# v0_1.net
KiCad netlist of a schematic drawn in EAGLE
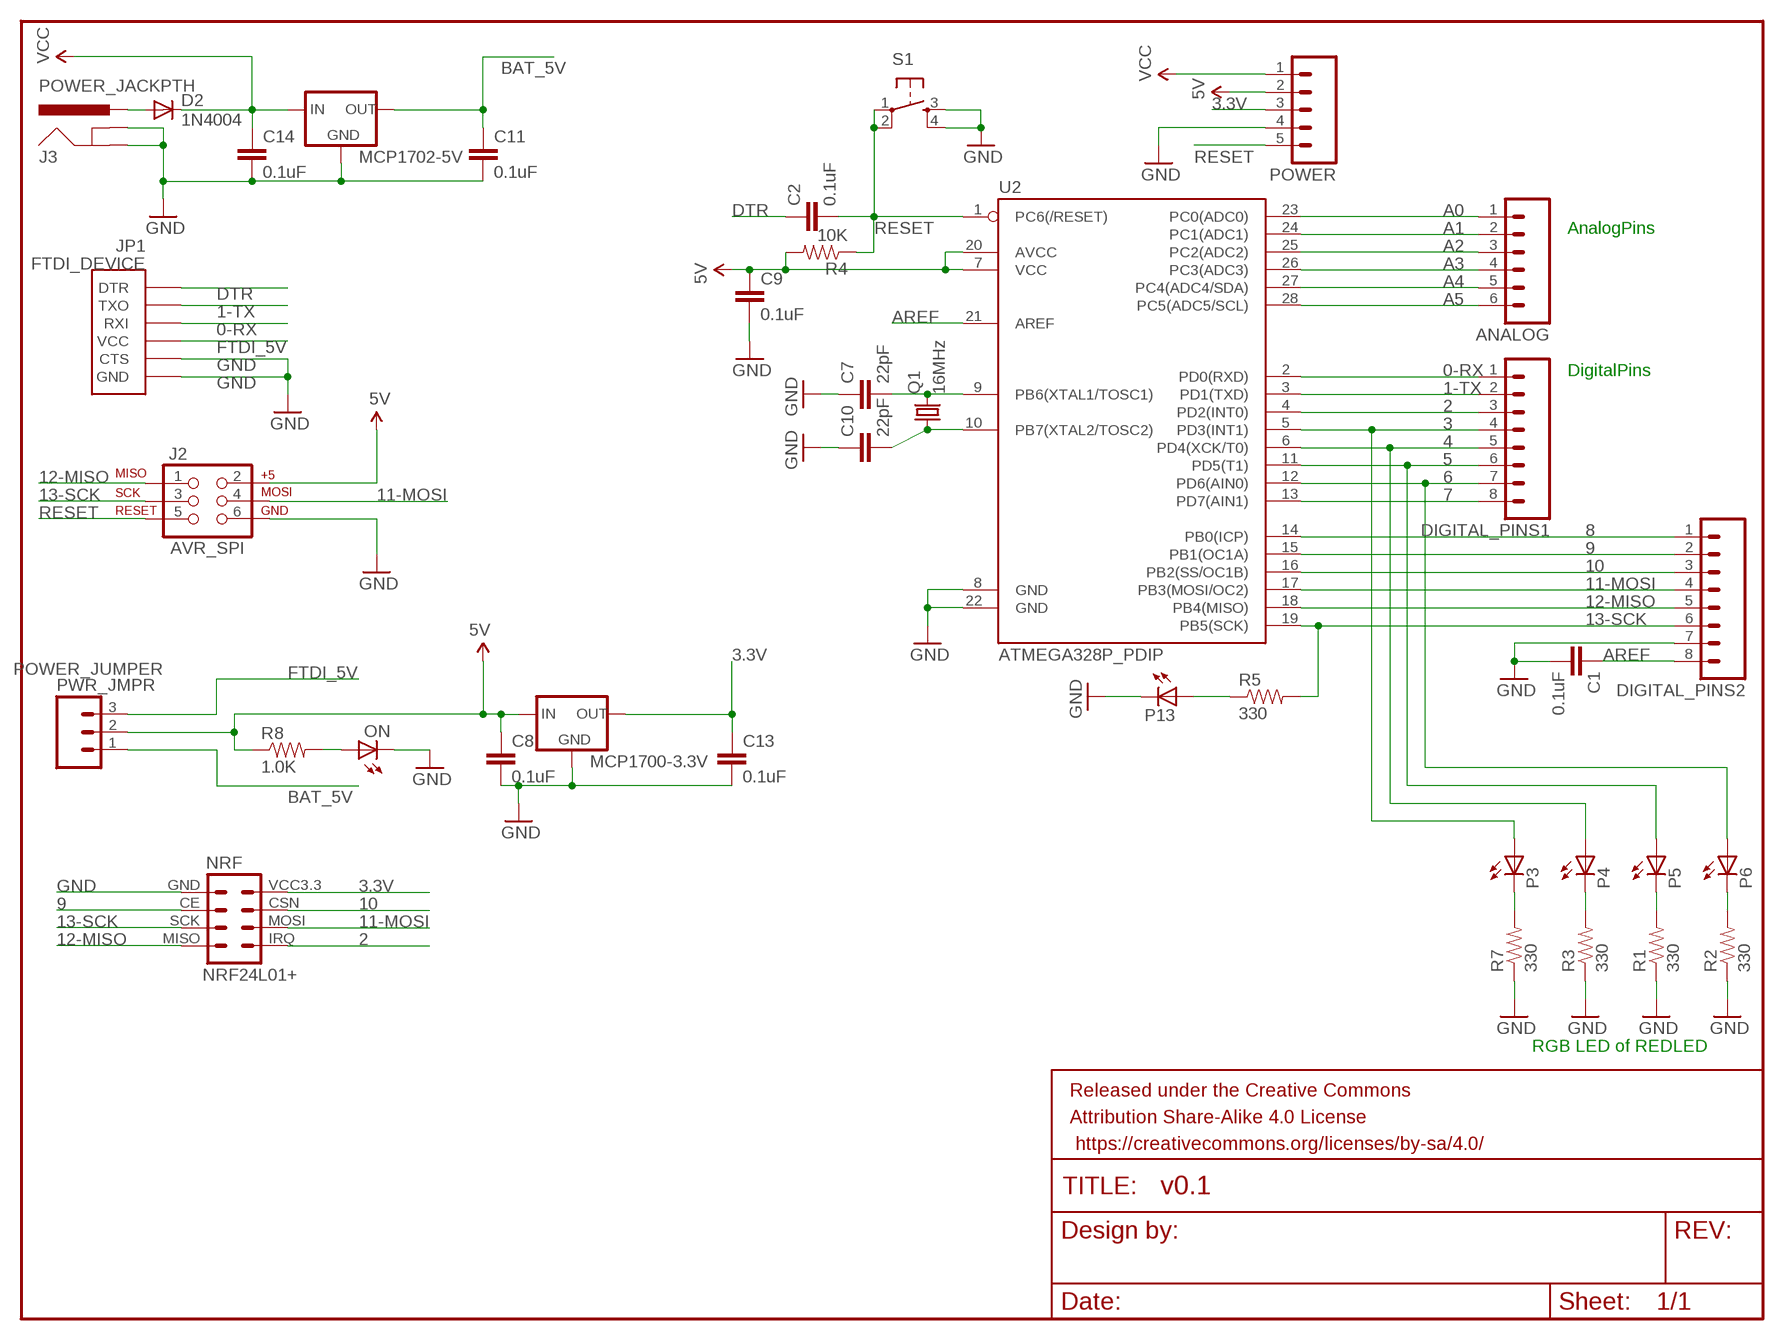
[diagram p0: schematic, sheet 1]

(export (version "E")
  (design (tool "Eeschema 10.0.6"))
  (components
    (comp (ref "ANALOG")
      (value "M06LOCK")
      (footprint "eagle-import:1X06_LOCK")
      (libsource (lib "eagle-import") (part "M06LOCK"))
    )
    (comp (ref "C1")
      (value "0.1uF")
      (footprint "eagle-import:CAP-PTH-SMALL")
      (libsource (lib "eagle-import") (part "CAPPTH"))
    )
    (comp (ref "C2")
      (value "0.1uF")
      (footprint "eagle-import:CAP-PTH-SMALL")
      (libsource (lib "eagle-import") (part "CAPPTH"))
    )
    (comp (ref "C7")
      (value "22pF")
      (footprint "eagle-import:CAP-PTH-SMALL")
      (libsource (lib "eagle-import") (part "CAPPTH"))
    )
    (comp (ref "C8")
      (value "0.1uF")
      (footprint "eagle-import:CAP-PTH-SMALL")
      (libsource (lib "eagle-import") (part "CAPPTH"))
    )
    (comp (ref "C9")
      (value "0.1uF")
      (footprint "eagle-import:CAP-PTH-SMALL")
      (libsource (lib "eagle-import") (part "CAPPTH"))
    )
    (comp (ref "C10")
      (value "22pF")
      (footprint "eagle-import:CAP-PTH-SMALL")
      (libsource (lib "eagle-import") (part "CAPPTH"))
    )
    (comp (ref "C11")
      (value "0.1uF")
      (footprint "eagle-import:CAP-PTH-SMALL")
      (libsource (lib "eagle-import") (part "CAPPTH"))
    )
    (comp (ref "C13")
      (value "0.1uF")
      (footprint "eagle-import:CAP-PTH-SMALL")
      (libsource (lib "eagle-import") (part "CAPPTH"))
    )
    (comp (ref "C14")
      (value "0.1uF")
      (footprint "eagle-import:CAP-PTH-SMALL")
      (libsource (lib "eagle-import") (part "CAPPTH"))
    )
    (comp (ref "D2")
      (value "1N4004")
      (footprint "eagle-import:DO41-10")
      (libsource (lib "eagle-import") (part "1N4004"))
    )
    (comp (ref "DIGITAL_PINS1")
      (value "M08LOCK")
      (footprint "eagle-import:1X08_LOCK")
      (libsource (lib "eagle-import") (part "M08LOCK"))
    )
    (comp (ref "DIGITAL_PINS2")
      (value "M08LOCK")
      (footprint "eagle-import:1X08_LOCK")
      (libsource (lib "eagle-import") (part "M08LOCK"))
    )
    (comp (ref "FRAME1")
      (value "FRAME-LETTER")
      (footprint "eagle-import:CREATIVE_COMMONS")
      (libsource (lib "eagle-import") (part "FRAME-LETTER"))
    )
    (comp (ref "J2")
      (value "AVR_SPI")
      (footprint "eagle-import:2X3")
      (libsource (lib "eagle-import") (part "AVR_SPI_PRG_6PTH"))
    )
    (comp (ref "J3")
      (value "POWER_JACKPTH")
      (footprint "eagle-import:POWER_JACK_PTH")
      (libsource (lib "eagle-import") (part "POWER_JACKPTH"))
    )
    (comp (ref "JP1")
      (value "FTDI_DEVICE")
      (footprint "eagle-import:FTDI_DEVICE_SIDE")
      (libsource (lib "eagle-import") (part "FTDI_DEVICE"))
    )
    (comp (ref "MCP1700-3.3V")
      (value "MCP1700INLINE")
      (footprint "eagle-import:TO92-INLINE")
      (libsource (lib "eagle-import") (part "MCP1700INLINE"))
    )
    (comp (ref "MCP1702-5V")
      (value "MCP1700INLINE")
      (footprint "eagle-import:TO92-INLINE")
      (libsource (lib "eagle-import") (part "MCP1700INLINE"))
    )
    (comp (ref "NRF")
      (value "NRF24L01+")
      (footprint "eagle-import:2X4")
      (libsource (lib "eagle-import") (part "NRF24L01+"))
    )
    (comp (ref "ON")
      (value "LED3MM")
      (footprint "eagle-import:LED3MM")
      (libsource (lib "eagle-import") (part "LED3MM"))
    )
    (comp (ref "P3")
      (value "LED5MM")
      (footprint "eagle-import:LED5MM")
      (libsource (lib "eagle-import") (part "LED5MM"))
    )
    (comp (ref "P4")
      (value "LED5MM")
      (footprint "eagle-import:LED5MM")
      (libsource (lib "eagle-import") (part "LED5MM"))
    )
    (comp (ref "P5")
      (value "LED5MM")
      (footprint "eagle-import:LED5MM")
      (libsource (lib "eagle-import") (part "LED5MM"))
    )
    (comp (ref "P6")
      (value "LED5MM")
      (footprint "eagle-import:LED5MM")
      (libsource (lib "eagle-import") (part "LED5MM"))
    )
    (comp (ref "P13")
      (value "LED3MM")
      (footprint "eagle-import:LED3MM")
      (libsource (lib "eagle-import") (part "LED3MM"))
    )
    (comp (ref "POWER")
      (value "M05LOCK")
      (footprint "eagle-import:1X05_LOCK")
      (libsource (lib "eagle-import") (part "M05LOCK"))
    )
    (comp (ref "PWR_JMPR")
      (value "M03LOCK")
      (footprint "eagle-import:1X03_LOCK")
      (libsource (lib "eagle-import") (part "M03LOCK"))
    )
    (comp (ref "Q1")
      (value "16MHz")
      (footprint "eagle-import:HC49_S")
      (libsource (lib "eagle-import") (part "CRYSTALHC49S"))
    )
    (comp (ref "R1")
      (value "330")
      (footprint "eagle-import:AXIAL-0.4")
      (libsource (lib "eagle-import") (part "RESISTORPTH-1/4W"))
    )
    (comp (ref "R2")
      (value "330")
      (footprint "eagle-import:AXIAL-0.4")
      (libsource (lib "eagle-import") (part "RESISTORPTH-1/4W"))
    )
    (comp (ref "R3")
      (value "330")
      (footprint "eagle-import:AXIAL-0.4")
      (libsource (lib "eagle-import") (part "RESISTORPTH-1/4W"))
    )
    (comp (ref "R4")
      (value "10K")
      (footprint "eagle-import:AXIAL-0.4")
      (libsource (lib "eagle-import") (part "RESISTORPTH-1/4W"))
    )
    (comp (ref "R5")
      (value "330")
      (footprint "eagle-import:AXIAL-0.4")
      (libsource (lib "eagle-import") (part "RESISTORPTH-1/4W"))
    )
    (comp (ref "R7")
      (value "330")
      (footprint "eagle-import:AXIAL-0.4")
      (libsource (lib "eagle-import") (part "RESISTORPTH-1/4W"))
    )
    (comp (ref "R8")
      (value "1.0K")
      (footprint "eagle-import:AXIAL-0.4")
      (libsource (lib "eagle-import") (part "RESISTORPTH-1/4W"))
    )
    (comp (ref "S1")
      (value "TAC_SWITCHPTH")
      (footprint "eagle-import:TACTILE-PTH")
      (libsource (lib "eagle-import") (part "TAC_SWITCHPTH"))
    )
    (comp (ref "U2")
      (value "ATMEGA328P_PDIP")
      (footprint "eagle-import:DIL28-3")
      (libsource (lib "eagle-import") (part "ATMEGA328P_PDIP"))
    )
  )
  (nets
    (net (code "1") (name "/0-RX") (class "Default")
      (node (ref "DIGITAL_PINS1") (pin "1") (pinfunction "1_1") (pintype "passive"))
      (node (ref "JP1") (pin "P$3") (pinfunction "RXI_P$3") (pintype "bidirectional"))
      (node (ref "U2") (pin "2") (pinfunction "PD0(RXD)_2") (pintype "bidirectional"))
    )
    (net (code "2") (name "/1-TX") (class "Default")
      (node (ref "DIGITAL_PINS1") (pin "2") (pinfunction "2_2") (pintype "passive"))
      (node (ref "JP1") (pin "P$2") (pinfunction "TXO_P$2") (pintype "bidirectional"))
      (node (ref "U2") (pin "3") (pinfunction "PD1(TXD)_3") (pintype "bidirectional"))
    )
    (net (code "3") (name "/2") (class "Default")
      (node (ref "DIGITAL_PINS1") (pin "3") (pinfunction "3_3") (pintype "passive"))
      (node (ref "NRF") (pin "IRQ") (pinfunction "IRQ_IRQ") (pintype "passive"))
      (node (ref "U2") (pin "4") (pinfunction "PD2(INT0)_4") (pintype "bidirectional"))
    )
    (net (code "4") (name "/3") (class "Default")
      (node (ref "DIGITAL_PINS1") (pin "4") (pinfunction "4_4") (pintype "passive"))
      (node (ref "P3") (pin "A") (pinfunction "A_A") (pintype "passive"))
      (node (ref "U2") (pin "5") (pinfunction "PD3(INT1)_5") (pintype "bidirectional"))
    )
    (net (code "5") (name "/3.3V") (class "Default")
      (node (ref "C13") (pin "1") (pinfunction "1_1") (pintype "passive"))
      (node (ref "MCP1700-3.3V") (pin "3") (pinfunction "OUT_3") (pintype "passive"))
      (node (ref "NRF") (pin "VCC3.3") (pinfunction "VCC_VCC3.3") (pintype "passive"))
      (node (ref "POWER") (pin "3") (pinfunction "3_3") (pintype "passive"))
    )
    (net (code "6") (name "/4") (class "Default")
      (node (ref "DIGITAL_PINS1") (pin "5") (pinfunction "5_5") (pintype "passive"))
      (node (ref "P4") (pin "A") (pinfunction "A_A") (pintype "passive"))
      (node (ref "U2") (pin "6") (pinfunction "PD4(XCK/T0)_6") (pintype "bidirectional"))
    )
    (net (code "7") (name "/5") (class "Default")
      (node (ref "DIGITAL_PINS1") (pin "6") (pinfunction "6_6") (pintype "passive"))
      (node (ref "P5") (pin "A") (pinfunction "A_A") (pintype "passive"))
      (node (ref "U2") (pin "11") (pinfunction "PD5(T1)_11") (pintype "bidirectional"))
    )
    (net (code "8") (name "/6") (class "Default")
      (node (ref "DIGITAL_PINS1") (pin "7") (pinfunction "7_7") (pintype "passive"))
      (node (ref "P6") (pin "A") (pinfunction "A_A") (pintype "passive"))
      (node (ref "U2") (pin "12") (pinfunction "PD6(AIN0)_12") (pintype "bidirectional"))
    )
    (net (code "9") (name "/7") (class "Default")
      (node (ref "DIGITAL_PINS1") (pin "8") (pinfunction "8_8") (pintype "passive"))
      (node (ref "U2") (pin "13") (pinfunction "PD7(AIN1)_13") (pintype "bidirectional"))
    )
    (net (code "10") (name "/8") (class "Default")
      (node (ref "DIGITAL_PINS2") (pin "1") (pinfunction "1_1") (pintype "passive"))
      (node (ref "U2") (pin "14") (pinfunction "PB0(ICP)_14") (pintype "bidirectional"))
    )
    (net (code "11") (name "/9") (class "Default")
      (node (ref "DIGITAL_PINS2") (pin "2") (pinfunction "2_2") (pintype "passive"))
      (node (ref "NRF") (pin "CE") (pinfunction "CE_CE") (pintype "passive"))
      (node (ref "U2") (pin "15") (pinfunction "PB1(OC1A)_15") (pintype "bidirectional"))
    )
    (net (code "12") (name "/10") (class "Default")
      (node (ref "DIGITAL_PINS2") (pin "3") (pinfunction "3_3") (pintype "passive"))
      (node (ref "NRF") (pin "CSN") (pinfunction "CSN_CSN") (pintype "passive"))
      (node (ref "U2") (pin "16") (pinfunction "PB2(SS/OC1B)_16") (pintype "bidirectional"))
    )
    (net (code "13") (name "/11-MOSI") (class "Default")
      (node (ref "DIGITAL_PINS2") (pin "4") (pinfunction "4_4") (pintype "passive"))
      (node (ref "J2") (pin "4") (pinfunction "4_4") (pintype "passive"))
      (node (ref "NRF") (pin "MOSI") (pinfunction "MOSI_MOSI") (pintype "passive"))
      (node (ref "U2") (pin "17") (pinfunction "PB3(MOSI/OC2)_17") (pintype "bidirectional"))
    )
    (net (code "14") (name "/12-MISO") (class "Default")
      (node (ref "DIGITAL_PINS2") (pin "5") (pinfunction "5_5") (pintype "passive"))
      (node (ref "J2") (pin "1") (pinfunction "1_1") (pintype "passive"))
      (node (ref "NRF") (pin "MISO") (pinfunction "MISO_MISO") (pintype "passive"))
      (node (ref "U2") (pin "18") (pinfunction "PB4(MISO)_18") (pintype "bidirectional"))
    )
    (net (code "15") (name "/13-SCK") (class "Default")
      (node (ref "DIGITAL_PINS2") (pin "6") (pinfunction "6_6") (pintype "passive"))
      (node (ref "J2") (pin "3") (pinfunction "3_3") (pintype "passive"))
      (node (ref "NRF") (pin "SCK") (pinfunction "SCK_SCK") (pintype "passive"))
      (node (ref "R5") (pin "P$2") (pinfunction "2_P$2") (pintype "passive"))
      (node (ref "U2") (pin "19") (pinfunction "PB5(SCK)_19") (pintype "bidirectional"))
    )
    (net (code "16") (name "/A0") (class "Default")
      (node (ref "ANALOG") (pin "1") (pinfunction "1_1") (pintype "passive"))
      (node (ref "U2") (pin "23") (pinfunction "PC0(ADC0)_23") (pintype "bidirectional"))
    )
    (net (code "17") (name "/A1") (class "Default")
      (node (ref "ANALOG") (pin "2") (pinfunction "2_2") (pintype "passive"))
      (node (ref "U2") (pin "24") (pinfunction "PC1(ADC1)_24") (pintype "bidirectional"))
    )
    (net (code "18") (name "/A2") (class "Default")
      (node (ref "ANALOG") (pin "3") (pinfunction "3_3") (pintype "passive"))
      (node (ref "U2") (pin "25") (pinfunction "PC2(ADC2)_25") (pintype "bidirectional"))
    )
    (net (code "19") (name "/A3") (class "Default")
      (node (ref "ANALOG") (pin "4") (pinfunction "4_4") (pintype "passive"))
      (node (ref "U2") (pin "26") (pinfunction "PC3(ADC3)_26") (pintype "bidirectional"))
    )
    (net (code "20") (name "/A4") (class "Default")
      (node (ref "ANALOG") (pin "5") (pinfunction "5_5") (pintype "passive"))
      (node (ref "U2") (pin "27") (pinfunction "PC4(ADC4/SDA)_27") (pintype "bidirectional"))
    )
    (net (code "21") (name "/A5") (class "Default")
      (node (ref "ANALOG") (pin "6") (pinfunction "6_6") (pintype "passive"))
      (node (ref "U2") (pin "28") (pinfunction "PC5(ADC5/SCL)_28") (pintype "bidirectional"))
    )
    (net (code "22") (name "/AREF") (class "Default")
      (node (ref "C1") (pin "1") (pinfunction "1_1") (pintype "passive"))
      (node (ref "DIGITAL_PINS2") (pin "8") (pinfunction "8_8") (pintype "passive"))
      (node (ref "U2") (pin "21") (pinfunction "AREF_21") (pintype "bidirectional"))
    )
    (net (code "23") (name "/BAT_5V") (class "Default")
      (node (ref "C11") (pin "1") (pinfunction "1_1") (pintype "passive"))
      (node (ref "MCP1702-5V") (pin "3") (pinfunction "OUT_3") (pintype "passive"))
      (node (ref "PWR_JMPR") (pin "1") (pinfunction "1_1") (pintype "passive"))
    )
    (net (code "24") (name "/DTR") (class "Default")
      (node (ref "C2") (pin "1") (pinfunction "1_1") (pintype "passive"))
      (node (ref "JP1") (pin "P$1") (pinfunction "DTR_P$1") (pintype "bidirectional"))
    )
    (net (code "25") (name "/FTDI_5V") (class "Default")
      (node (ref "JP1") (pin "P$4") (pinfunction "VCC_P$4") (pintype "bidirectional"))
      (node (ref "PWR_JMPR") (pin "3") (pinfunction "3_3") (pintype "passive"))
    )
    (net (code "26") (name "/RESET") (class "Default")
      (node (ref "C2") (pin "2") (pinfunction "2_2") (pintype "passive"))
      (node (ref "J2") (pin "5") (pinfunction "5_5") (pintype "passive"))
      (node (ref "POWER") (pin "5") (pinfunction "5_5") (pintype "passive"))
      (node (ref "R4") (pin "P$1") (pinfunction "1_P$1") (pintype "passive"))
      (node (ref "S1") (pin "1") (pinfunction "1_1") (pintype "passive"))
      (node (ref "S1") (pin "2") (pinfunction "2_2") (pintype "passive"))
      (node (ref "U2") (pin "1") (pinfunction "PC6(/RESET)_1") (pintype "bidirectional"))
    )
    (net (code "27") (name "5V") (class "Default")
      (node (ref "C8") (pin "1") (pinfunction "1_1") (pintype "passive"))
      (node (ref "C9") (pin "1") (pinfunction "1_1") (pintype "passive"))
      (node (ref "J2") (pin "2") (pinfunction "2_2") (pintype "passive"))
      (node (ref "MCP1700-3.3V") (pin "2") (pinfunction "IN_2") (pintype "input"))
      (node (ref "POWER") (pin "2") (pinfunction "2_2") (pintype "passive"))
      (node (ref "PWR_JMPR") (pin "2") (pinfunction "2_2") (pintype "passive"))
      (node (ref "R4") (pin "P$2") (pinfunction "2_P$2") (pintype "passive"))
      (node (ref "R8") (pin "P$1") (pinfunction "1_P$1") (pintype "passive"))
      (node (ref "U2") (pin "20") (pinfunction "AVCC_20") (pintype "bidirectional"))
      (node (ref "U2") (pin "7") (pinfunction "VCC_7") (pintype "bidirectional"))
    )
    (net (code "28") (name "GND") (class "Default")
      (node (ref "C1") (pin "2") (pinfunction "2_2") (pintype "passive"))
      (node (ref "C10") (pin "1") (pinfunction "1_1") (pintype "passive"))
      (node (ref "C11") (pin "2") (pinfunction "2_2") (pintype "passive"))
      (node (ref "C13") (pin "2") (pinfunction "2_2") (pintype "passive"))
      (node (ref "C14") (pin "2") (pinfunction "2_2") (pintype "passive"))
      (node (ref "C7") (pin "1") (pinfunction "1_1") (pintype "passive"))
      (node (ref "C8") (pin "2") (pinfunction "2_2") (pintype "passive"))
      (node (ref "C9") (pin "2") (pinfunction "2_2") (pintype "passive"))
      (node (ref "DIGITAL_PINS2") (pin "7") (pinfunction "7_7") (pintype "passive"))
      (node (ref "J2") (pin "6") (pinfunction "6_6") (pintype "passive"))
      (node (ref "J3") (pin "GND") (pinfunction "GND_GND") (pintype "bidirectional"))
      (node (ref "J3") (pin "GNDBREAK") (pinfunction "GNDBREAK_GNDBREAK") (pintype "bidirectional"))
      (node (ref "JP1") (pin "P$5") (pinfunction "CTS_P$5") (pintype "bidirectional"))
      (node (ref "JP1") (pin "P$6") (pinfunction "GND_P$6") (pintype "bidirectional"))
      (node (ref "MCP1700-3.3V") (pin "1") (pinfunction "GND_1") (pintype "input"))
      (node (ref "MCP1702-5V") (pin "1") (pinfunction "GND_1") (pintype "input"))
      (node (ref "NRF") (pin "GND") (pinfunction "GND_GND") (pintype "passive"))
      (node (ref "ON") (pin "K") (pinfunction "C_K") (pintype "passive"))
      (node (ref "P13") (pin "K") (pinfunction "C_K") (pintype "passive"))
      (node (ref "POWER") (pin "4") (pinfunction "4_4") (pintype "passive"))
      (node (ref "R1") (pin "P$1") (pinfunction "1_P$1") (pintype "passive"))
      (node (ref "R2") (pin "P$1") (pinfunction "1_P$1") (pintype "passive"))
      (node (ref "R3") (pin "P$1") (pinfunction "1_P$1") (pintype "passive"))
      (node (ref "R7") (pin "P$1") (pinfunction "1_P$1") (pintype "passive"))
      (node (ref "S1") (pin "3") (pinfunction "3_3") (pintype "passive"))
      (node (ref "S1") (pin "4") (pinfunction "4_4") (pintype "passive"))
      (node (ref "U2") (pin "22") (pinfunction "GND_22") (pintype "bidirectional"))
      (node (ref "U2") (pin "8") (pinfunction "GND_8") (pintype "bidirectional"))
    )
    (net (code "29") (name "Net-(D2-PadA)") (class "Default")
      (node (ref "D2") (pin "A") (pinfunction "A_A") (pintype "passive"))
      (node (ref "J3") (pin "PWR") (pinfunction "PWR_PWR") (pintype "bidirectional"))
    )
    (net (code "30") (name "Net-(P3-C)") (class "Default")
      (node (ref "P3") (pin "K") (pinfunction "C_K") (pintype "passive"))
      (node (ref "R7") (pin "P$2") (pinfunction "2_P$2") (pintype "passive"))
    )
    (net (code "31") (name "Net-(P4-C)") (class "Default")
      (node (ref "P4") (pin "K") (pinfunction "C_K") (pintype "passive"))
      (node (ref "R3") (pin "P$2") (pinfunction "2_P$2") (pintype "passive"))
    )
    (net (code "32") (name "Net-(P5-C)") (class "Default")
      (node (ref "P5") (pin "K") (pinfunction "C_K") (pintype "passive"))
      (node (ref "R1") (pin "P$2") (pinfunction "2_P$2") (pintype "passive"))
    )
    (net (code "33") (name "Net-(P6-C)") (class "Default")
      (node (ref "P6") (pin "K") (pinfunction "C_K") (pintype "passive"))
      (node (ref "R2") (pin "P$2") (pinfunction "2_P$2") (pintype "passive"))
    )
    (net (code "34") (name "Net-(R5-1)") (class "Default")
      (node (ref "P13") (pin "A") (pinfunction "A_A") (pintype "passive"))
      (node (ref "R5") (pin "P$1") (pinfunction "1_P$1") (pintype "passive"))
    )
    (net (code "35") (name "Net-(R8-2)") (class "Default")
      (node (ref "ON") (pin "A") (pinfunction "A_A") (pintype "passive"))
      (node (ref "R8") (pin "P$2") (pinfunction "2_P$2") (pintype "passive"))
    )
    (net (code "36") (name "Net-(U2-PB6(XTAL1{slash}TOSC1))") (class "Default")
      (node (ref "C7") (pin "2") (pinfunction "2_2") (pintype "passive"))
      (node (ref "Q1") (pin "2") (pinfunction "2_2") (pintype "passive"))
      (node (ref "U2") (pin "9") (pinfunction "PB6(XTAL1/TOSC1)_9") (pintype "bidirectional"))
    )
    (net (code "37") (name "Net-(U2-PB7(XTAL2{slash}TOSC2))") (class "Default")
      (node (ref "C10") (pin "2") (pinfunction "2_2") (pintype "passive"))
      (node (ref "Q1") (pin "1") (pinfunction "1_1") (pintype "passive"))
      (node (ref "U2") (pin "10") (pinfunction "PB7(XTAL2/TOSC2)_10") (pintype "bidirectional"))
    )
    (net (code "38") (name "VCC") (class "Default")
      (node (ref "C14") (pin "1") (pinfunction "1_1") (pintype "passive"))
      (node (ref "D2") (pin "C") (pinfunction "C_C") (pintype "passive"))
      (node (ref "MCP1702-5V") (pin "2") (pinfunction "IN_2") (pintype "input"))
      (node (ref "POWER") (pin "1") (pinfunction "1_1") (pintype "passive"))
    )
  )
)
